# ESP32_Relay_Card_Power.net
KiCad netlist of a schematic drawn in Altium Designer
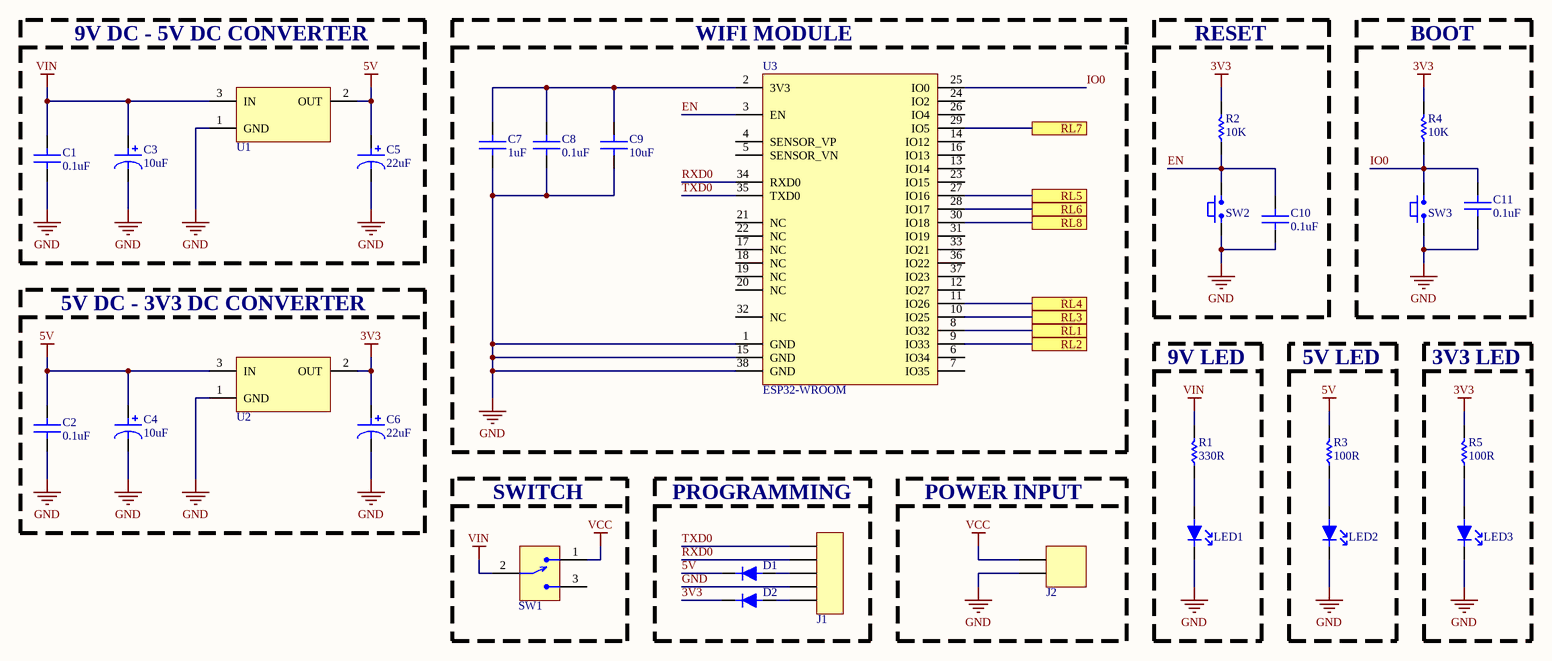
[diagram p0: ESP32 Relay Card Power.SchDoc]

(export (version "E")
  (design (tool "Eeschema 10.0.6"))
  (components
    (comp (ref "C1")
      (value "0.1uF")
      (footprint "CAP 0805")
      (description "CAP CER 0.1UF 50V X7R 0805")
      (fields (field (name "Comment") "CC0805KRX7R9BB104"))
      (libsource (lib "ESP32 Relay Card") (part "CAP CER 0.1UF 0805 SMD"))
    )
    (comp (ref "C2")
      (value "0.1uF")
      (footprint "CAP 0805")
      (description "CAP CER 0.1UF 50V X7R 0805")
      (fields (field (name "Comment") "CC0805KRX7R9BB104"))
      (libsource (lib "ESP32 Relay Card") (part "CAP CER 0.1UF 0805 SMD"))
    )
    (comp (ref "C3")
      (value "10uF")
      (footprint "CAP ALUM 10UF")
      (description "CAP ALUM 10UF 20% 16V SMD")
      (fields (field (name "Comment") "875105359001"))
      (libsource (lib "ESP32 Relay Card") (part "CAP ALUM 10UF SMD"))
    )
    (comp (ref "C4")
      (value "10uF")
      (footprint "CAP ALUM 10UF")
      (description "CAP ALUM 10UF 20% 16V SMD")
      (fields (field (name "Comment") "875105359001"))
      (libsource (lib "ESP32 Relay Card") (part "CAP ALUM 10UF SMD"))
    )
    (comp (ref "C5")
      (value "22uF")
      (footprint "CAP ALUM 22UF")
      (description "CAP ALUM 22UF 20% 20V SMD")
      (fields (field (name "Comment") "A766EB226M1DLAE060"))
      (libsource (lib "ESP32 Relay Card") (part "CAP ALUM 22UF SMD"))
    )
    (comp (ref "C6")
      (value "22uF")
      (footprint "CAP ALUM 22UF")
      (description "CAP ALUM 22UF 20% 20V SMD")
      (fields (field (name "Comment") "A766EB226M1DLAE060"))
      (libsource (lib "ESP32 Relay Card") (part "CAP ALUM 22UF SMD"))
    )
    (comp (ref "C7")
      (value "1uF")
      (footprint "CAP 0805")
      (description "CAP CER 1UF 50V X7R 0805")
      (fields (field (name "Comment") "CC0805KKX7R9BB105"))
      (libsource (lib "ESP32 Relay Card") (part "CAP CER 1UF 0805 SMD"))
    )
    (comp (ref "C8")
      (value "0.1uF")
      (footprint "CAP 0805")
      (description "CAP CER 0.1UF 50V X7R 0805")
      (fields (field (name "Comment") "CC0805KRX7R9BB104"))
      (libsource (lib "ESP32 Relay Card") (part "CAP CER 0.1UF 0805 SMD"))
    )
    (comp (ref "C9")
      (value "10uF")
      (footprint "CAP 0805")
      (description "CAP CER 10UF 25V X5R 0805")
      (fields (field (name "Comment") "CC0805KKX5R8BB106"))
      (libsource (lib "ESP32 Relay Card") (part "CAP CER 10UF 0805 SMD"))
    )
    (comp (ref "C10")
      (value "0.1uF")
      (footprint "CAP 0805")
      (description "CAP CER 0.1UF 50V X7R 0805")
      (fields (field (name "Comment") "CC0805KRX7R9BB104"))
      (libsource (lib "ESP32 Relay Card") (part "CAP CER 0.1UF 0805 SMD"))
    )
    (comp (ref "C11")
      (value "0.1uF")
      (footprint "CAP 0805")
      (description "CAP CER 0.1UF 50V X7R 0805")
      (fields (field (name "Comment") "CC0805KRX7R9BB104"))
      (libsource (lib "ESP32 Relay Card") (part "CAP CER 0.1UF 0805 SMD"))
    )
    (comp (ref "D1")
      (value "1N5819W")
      (footprint "SOD-123F")
      (description "DIODE SCHOTTKY 40V 1A SOD-123F")
      (libsource (lib "ESP32 Relay Card") (part "SCHOTTKY DIODE SMD"))
    )
    (comp (ref "D2")
      (value "1N5819W")
      (footprint "SOD-123F")
      (description "DIODE SCHOTTKY 40V 1A SOD-123F")
      (libsource (lib "ESP32 Relay Card") (part "SCHOTTKY DIODE SMD"))
    )
    (comp (ref "J1")
      (value "61300511121")
      (footprint "HEADER")
      (description "CONN HEADER 5POS 2.54MM")
      (libsource (lib "ESP32 Relay Card") (part "HEADER 5POS TH"))
    )
    (comp (ref "J2")
      (value "TB006-508-02BE")
      (footprint "2POS CONNECTOR")
      (description "TERM BLK 2P 5.08 PCB")
      (libsource (lib "ESP32 Relay Card") (part "2POS CONNECTOR"))
    )
    (comp (ref "LED1")
      (value "150080VS75000")
      (footprint "LED 0805 SMD")
      (description "LED GREEN 0805 SMD")
      (libsource (lib "ESP32 Relay Card") (part "GREEN LED 0805 SMD"))
    )
    (comp (ref "LED2")
      (value "150080VS75000")
      (footprint "LED 0805 SMD")
      (description "LED GREEN 0805 SMD")
      (libsource (lib "ESP32 Relay Card") (part "GREEN LED 0805 SMD"))
    )
    (comp (ref "LED3")
      (value "150080VS75000")
      (footprint "LED 0805 SMD")
      (description "LED GREEN 0805 SMD")
      (libsource (lib "ESP32 Relay Card") (part "GREEN LED 0805 SMD"))
    )
    (comp (ref "R1")
      (value "330R")
      (footprint "RES 0603")
      (description "RES 330 OHM 1% 1/5W 0603")
      (fields (field (name "Comment") "CRGH0603F330R"))
      (libsource (lib "ESP32 Relay Card") (part "RES 330 OHM 0603 SMD"))
    )
    (comp (ref "R2")
      (value "10K")
      (footprint "RES 0603")
      (description "RES 10K OHM 5% 1/5W 0603")
      (fields (field (name "Comment") "CRGH0603J10K"))
      (libsource (lib "ESP32 Relay Card") (part "RES 10K OHM 0603 SMD"))
    )
    (comp (ref "R3")
      (value "100R")
      (footprint "RES 0603")
      (description "RES 100 OHM 5% 1/5W 0603")
      (fields (field (name "Comment") "CRGH0603J100R"))
      (libsource (lib "ESP32 Relay Card") (part "RES 100 OHM 0603 SMD"))
    )
    (comp (ref "R4")
      (value "10K")
      (footprint "RES 0603")
      (description "RES 10K OHM 5% 1/5W 0603")
      (fields (field (name "Comment") "CRGH0603J10K"))
      (libsource (lib "ESP32 Relay Card") (part "RES 10K OHM 0603 SMD"))
    )
    (comp (ref "R5")
      (value "100R")
      (footprint "RES 0603")
      (description "RES 100 OHM 5% 1/5W 0603")
      (fields (field (name "Comment") "CRGH0603J100R"))
      (libsource (lib "ESP32 Relay Card") (part "RES 100 OHM 0603 SMD"))
    )
    (comp (ref "SW1")
      (value "500SSP1S2M2QEA")
      (footprint "TACTICLE SWITCH TH")
      (description "SWITCH SLIDE 5A 120V")
      (libsource (lib "ESP32 Relay Card") (part "SLIDE SWITCH TH"))
    )
    (comp (ref "SW2")
      (value "PTS636SM43SMTR LFS")
      (footprint "TACTICLE SWITCH")
      (description "SWITCH TACTILE 0.05A 12V")
      (libsource (lib "ESP32 Relay Card") (part "TACTILE SWITCH SMD"))
    )
    (comp (ref "SW3")
      (value "PTS636SM43SMTR LFS")
      (footprint "TACTICLE SWITCH")
      (description "SWITCH TACTILE 0.05A 12V")
      (libsource (lib "ESP32 Relay Card") (part "TACTILE SWITCH SMD"))
    )
    (comp (ref "U1")
      (value "AMS1117-5.0")
      (footprint "SOT223")
      (description "IC LDO REG 5V 1A SOT223")
      (libsource (lib "ESP32 Relay Card") (part "LDO REG 5V 1A SMD"))
    )
    (comp (ref "U2")
      (value "AMS1117-3.3")
      (footprint "SOT223")
      (description "IC LDO REG 3.3V 1A SOT223")
      (libsource (lib "ESP32 Relay Card") (part "LDO REG 3V3 1A SMD"))
    )
    (comp (ref "U3")
      (value "ESP32-WROOM")
      (footprint "ESP32")
      (description "RF TXRX MOD BT WIFI TH SMD")
      (fields (field (name "Comment") "ESP32-WROOM-32E-H4"))
      (libsource (lib "ESP32 Relay Card") (part "ESP32-WROOM-32E"))
    )
  )
  (nets
    (net (code "1") (name "/EN") (class "Default")
      (node (ref "C10") (pin "2") (pintype "passive"))
      (node (ref "R2") (pin "1") (pintype "passive"))
      (node (ref "SW2") (pin "2") (pintype "passive"))
      (node (ref "U3") (pin "3") (pinfunction "EN_3") (pintype "passive"))
    )
    (net (code "2") (name "/IO0") (class "Default")
      (node (ref "C11") (pin "2") (pintype "passive"))
      (node (ref "R4") (pin "1") (pintype "passive"))
      (node (ref "SW3") (pin "2") (pintype "passive"))
      (node (ref "U3") (pin "25") (pinfunction "IO0_25") (pintype "passive"))
    )
    (net (code "3") (name "/RL1") (class "Default")
      (node (ref "U3") (pin "8") (pinfunction "IO32_8") (pintype "passive"))
    )
    (net (code "4") (name "/RL2") (class "Default")
      (node (ref "U3") (pin "9") (pinfunction "IO33_9") (pintype "passive"))
    )
    (net (code "5") (name "/RL3") (class "Default")
      (node (ref "U3") (pin "10") (pinfunction "IO25_10") (pintype "passive"))
    )
    (net (code "6") (name "/RL4") (class "Default")
      (node (ref "U3") (pin "11") (pinfunction "IO26_11") (pintype "passive"))
    )
    (net (code "7") (name "/RL5") (class "Default")
      (node (ref "U3") (pin "27") (pinfunction "IO16_27") (pintype "passive"))
    )
    (net (code "8") (name "/RL6") (class "Default")
      (node (ref "U3") (pin "28") (pinfunction "IO17_28") (pintype "passive"))
    )
    (net (code "9") (name "/RL7") (class "Default")
      (node (ref "U3") (pin "29") (pinfunction "IO5_29") (pintype "passive"))
    )
    (net (code "10") (name "/RL8") (class "Default")
      (node (ref "U3") (pin "30") (pinfunction "IO18_30") (pintype "passive"))
    )
    (net (code "11") (name "/RXD0") (class "Default")
      (node (ref "J1") (pin "2") (pintype "passive"))
      (node (ref "U3") (pin "34") (pinfunction "RXD0_34") (pintype "passive"))
    )
    (net (code "12") (name "/TXD0") (class "Default")
      (node (ref "J1") (pin "1") (pintype "passive"))
      (node (ref "U3") (pin "35") (pinfunction "TXD0_35") (pintype "passive"))
    )
    (net (code "13") (name "3V3") (class "Default")
      (node (ref "C6") (pin "1") (pintype "passive"))
      (node (ref "D2") (pin "2") (pintype "passive"))
      (node (ref "R2") (pin "2") (pintype "passive"))
      (node (ref "R4") (pin "2") (pintype "passive"))
      (node (ref "R5") (pin "2") (pintype "passive"))
      (node (ref "U2") (pin "2") (pinfunction "OUT_2") (pintype "passive"))
    )
    (net (code "14") (name "5V") (class "Default")
      (node (ref "C2") (pin "2") (pintype "passive"))
      (node (ref "C4") (pin "1") (pintype "passive"))
      (node (ref "C5") (pin "1") (pintype "passive"))
      (node (ref "D1") (pin "2") (pintype "passive"))
      (node (ref "R3") (pin "2") (pintype "passive"))
      (node (ref "U1") (pin "2") (pinfunction "OUT_2") (pintype "passive"))
      (node (ref "U2") (pin "3") (pinfunction "IN_3") (pintype "passive"))
    )
    (net (code "15") (name "GND") (class "Default")
      (node (ref "C1") (pin "1") (pintype "passive"))
      (node (ref "C10") (pin "1") (pintype "passive"))
      (node (ref "C11") (pin "1") (pintype "passive"))
      (node (ref "C2") (pin "1") (pintype "passive"))
      (node (ref "C3") (pin "2") (pintype "passive"))
      (node (ref "C4") (pin "2") (pintype "passive"))
      (node (ref "C5") (pin "2") (pintype "passive"))
      (node (ref "C6") (pin "2") (pintype "passive"))
      (node (ref "C7") (pin "1") (pintype "passive"))
      (node (ref "C8") (pin "1") (pintype "passive"))
      (node (ref "C9") (pin "1") (pintype "passive"))
      (node (ref "J1") (pin "4") (pintype "passive"))
      (node (ref "J2") (pin "2") (pintype "passive"))
      (node (ref "LED1") (pin "2") (pintype "passive"))
      (node (ref "LED2") (pin "2") (pintype "passive"))
      (node (ref "LED3") (pin "2") (pintype "passive"))
      (node (ref "SW2") (pin "1") (pintype "passive"))
      (node (ref "SW3") (pin "1") (pintype "passive"))
      (node (ref "U1") (pin "1") (pinfunction "GND_1") (pintype "passive"))
      (node (ref "U2") (pin "1") (pinfunction "GND_1") (pintype "passive"))
      (node (ref "U3") (pin "1") (pinfunction "GND_1") (pintype "passive"))
      (node (ref "U3") (pin "15") (pinfunction "GND_15") (pintype "passive"))
      (node (ref "U3") (pin "38") (pinfunction "GND_38") (pintype "passive"))
    )
    (net (code "16") (name "Net-(D1-Pad1)") (class "Default")
      (node (ref "D1") (pin "1") (pintype "passive"))
      (node (ref "J1") (pin "3") (pintype "passive"))
    )
    (net (code "17") (name "Net-(D2-Pad1)") (class "Default")
      (node (ref "D2") (pin "1") (pintype "passive"))
      (node (ref "J1") (pin "5") (pintype "passive"))
    )
    (net (code "18") (name "Net-(LED1-Pad1)") (class "Default")
      (node (ref "LED1") (pin "1") (pintype "passive"))
      (node (ref "R1") (pin "1") (pinfunction "1_1") (pintype "passive"))
    )
    (net (code "19") (name "Net-(LED2-Pad1)") (class "Default")
      (node (ref "LED2") (pin "1") (pintype "passive"))
      (node (ref "R3") (pin "1") (pintype "passive"))
    )
    (net (code "20") (name "Net-(LED3-Pad1)") (class "Default")
      (node (ref "LED3") (pin "1") (pintype "passive"))
      (node (ref "R5") (pin "1") (pintype "passive"))
    )
    (net (code "21") (name "Net-(U3-3V3)") (class "Default")
      (node (ref "C7") (pin "2") (pintype "passive"))
      (node (ref "C8") (pin "2") (pintype "passive"))
      (node (ref "C9") (pin "2") (pintype "passive"))
      (node (ref "U3") (pin "2") (pinfunction "3V3_2") (pintype "passive"))
    )
    (net (code "22") (name "VCC") (class "Default")
      (node (ref "J2") (pin "1") (pintype "passive"))
      (node (ref "SW1") (pin "1") (pinfunction "1_1") (pintype "passive"))
    )
    (net (code "23") (name "VIN") (class "Default")
      (node (ref "C1") (pin "2") (pintype "passive"))
      (node (ref "C3") (pin "1") (pintype "passive"))
      (node (ref "R1") (pin "2") (pinfunction "2_2") (pintype "passive"))
      (node (ref "SW1") (pin "2") (pinfunction "2_2") (pintype "passive"))
      (node (ref "U1") (pin "3") (pinfunction "IN_3") (pintype "passive"))
    )
    (net (code "24") (name "unconnected-(SW1-Pad3)") (class "Default")
      (node (ref "SW1") (pin "3") (pinfunction "3_3") (pintype "passive"))
    )
    (net (code "25") (name "unconnected-(U3-IO2-Pad24)") (class "Default")
      (node (ref "U3") (pin "24") (pinfunction "IO2_24") (pintype "passive"))
    )
    (net (code "26") (name "unconnected-(U3-IO4-Pad26)") (class "Default")
      (node (ref "U3") (pin "26") (pinfunction "IO4_26") (pintype "passive"))
    )
    (net (code "27") (name "unconnected-(U3-IO12-Pad14)") (class "Default")
      (node (ref "U3") (pin "14") (pinfunction "IO12_14") (pintype "passive"))
    )
    (net (code "28") (name "unconnected-(U3-IO13-Pad16)") (class "Default")
      (node (ref "U3") (pin "16") (pinfunction "IO13_16") (pintype "passive"))
    )
    (net (code "29") (name "unconnected-(U3-IO14-Pad13)") (class "Default")
      (node (ref "U3") (pin "13") (pinfunction "IO14_13") (pintype "passive"))
    )
    (net (code "30") (name "unconnected-(U3-IO15-Pad23)") (class "Default")
      (node (ref "U3") (pin "23") (pinfunction "IO15_23") (pintype "passive"))
    )
    (net (code "31") (name "unconnected-(U3-IO19-Pad31)") (class "Default")
      (node (ref "U3") (pin "31") (pinfunction "IO19_31") (pintype "passive"))
    )
    (net (code "32") (name "unconnected-(U3-IO21-Pad33)") (class "Default")
      (node (ref "U3") (pin "33") (pinfunction "IO21_33") (pintype "passive"))
    )
    (net (code "33") (name "unconnected-(U3-IO22-Pad36)") (class "Default")
      (node (ref "U3") (pin "36") (pinfunction "IO22_36") (pintype "passive"))
    )
    (net (code "34") (name "unconnected-(U3-IO23-Pad37)") (class "Default")
      (node (ref "U3") (pin "37") (pinfunction "IO23_37") (pintype "passive"))
    )
    (net (code "35") (name "unconnected-(U3-IO27-Pad12)") (class "Default")
      (node (ref "U3") (pin "12") (pinfunction "IO27_12") (pintype "passive"))
    )
    (net (code "36") (name "unconnected-(U3-IO34-Pad6)") (class "Default")
      (node (ref "U3") (pin "6") (pinfunction "IO34_6") (pintype "passive"))
    )
    (net (code "37") (name "unconnected-(U3-IO35-Pad7)") (class "Default")
      (node (ref "U3") (pin "7") (pinfunction "IO35_7") (pintype "passive"))
    )
    (net (code "38") (name "unconnected-(U3-NC-Pad17)") (class "Default")
      (node (ref "U3") (pin "17") (pinfunction "NC_17") (pintype "passive"))
    )
    (net (code "39") (name "unconnected-(U3-NC-Pad18)") (class "Default")
      (node (ref "U3") (pin "18") (pinfunction "NC_18") (pintype "passive"))
    )
    (net (code "40") (name "unconnected-(U3-NC-Pad19)") (class "Default")
      (node (ref "U3") (pin "19") (pinfunction "NC_19") (pintype "passive"))
    )
    (net (code "41") (name "unconnected-(U3-NC-Pad20)") (class "Default")
      (node (ref "U3") (pin "20") (pinfunction "NC_20") (pintype "passive"))
    )
    (net (code "42") (name "unconnected-(U3-NC-Pad21)") (class "Default")
      (node (ref "U3") (pin "21") (pinfunction "NC_21") (pintype "passive"))
    )
    (net (code "43") (name "unconnected-(U3-NC-Pad22)") (class "Default")
      (node (ref "U3") (pin "22") (pinfunction "NC_22") (pintype "passive"))
    )
    (net (code "44") (name "unconnected-(U3-NC-Pad32)") (class "Default")
      (node (ref "U3") (pin "32") (pinfunction "NC_32") (pintype "passive"))
    )
    (net (code "45") (name "unconnected-(U3-SENSOR_VN-Pad5)") (class "Default")
      (node (ref "U3") (pin "5") (pinfunction "SENSOR_VN_5") (pintype "passive"))
    )
    (net (code "46") (name "unconnected-(U3-SENSOR_VP-Pad4)") (class "Default")
      (node (ref "U3") (pin "4") (pinfunction "SENSOR_VP_4") (pintype "passive"))
    )
  )
)
